# CPU.net
KiCad netlist of a schematic drawn in Altium Designer
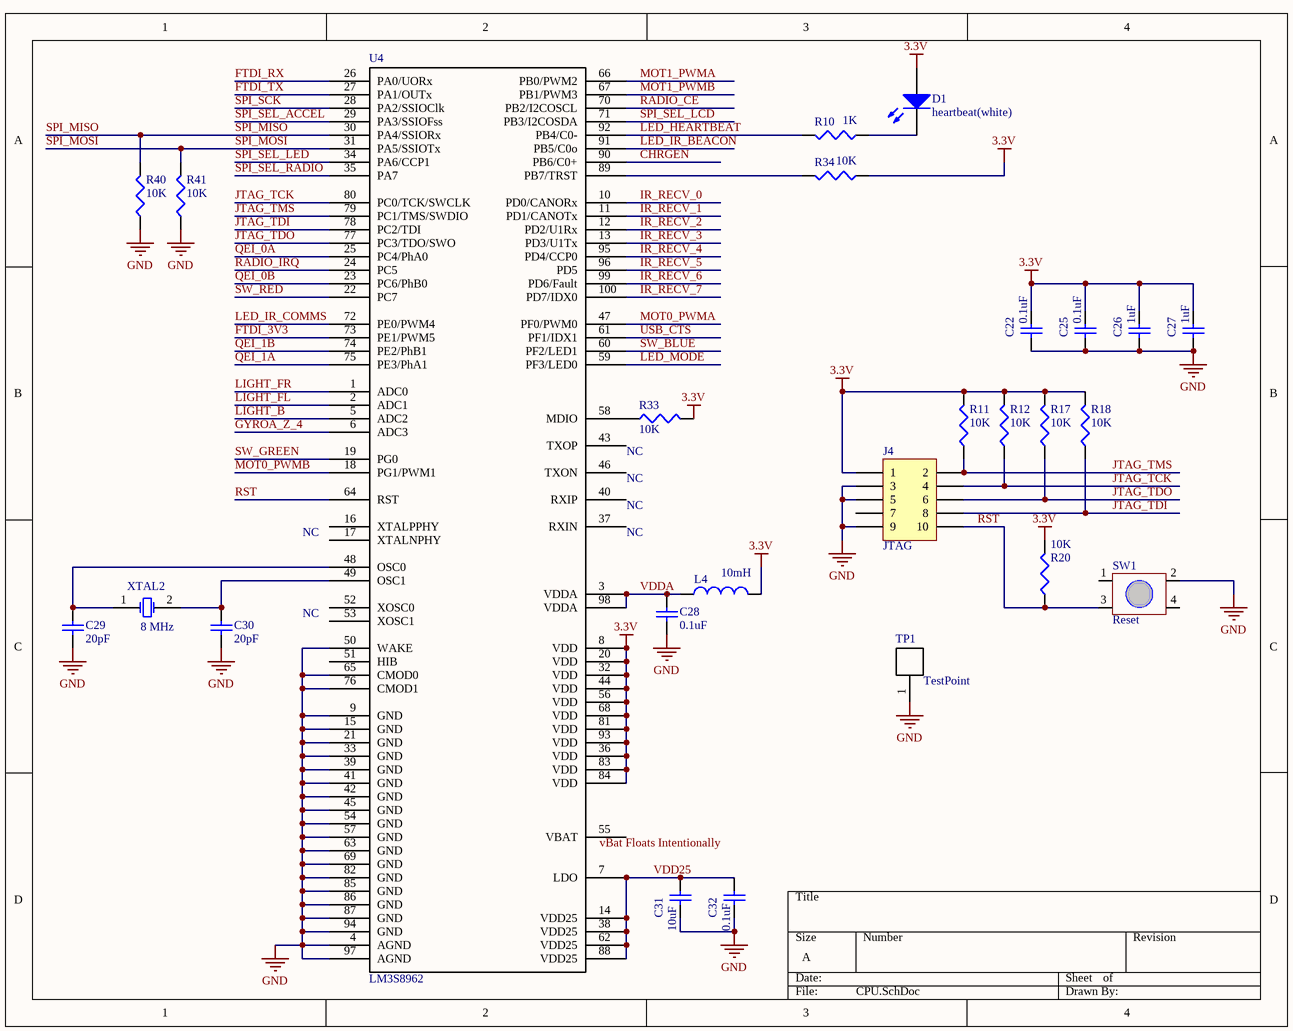
[diagram p0: CPU.SchDoc]

(export (version "E")
  (design (tool "Eeschema 10.0.6"))
  (components
    (comp (ref "C22")
      (value "0.1uF")
      (footprint "CAPC1005L")
      (description "Capacitor (Semiconductor SIM Model)")
      (fields (field (name "Comment") "Cap Semi") (field (name "PUBLISHER") "Altium Limited"))
      (libsource (lib "Miscellaneous Devices") (part "Cap Semi"))
    )
    (comp (ref "C25")
      (value "0.1uF")
      (footprint "CAPC1005L")
      (description "Capacitor (Semiconductor SIM Model)")
      (fields (field (name "Comment") "Cap Semi") (field (name "PUBLISHER") "Altium Limited"))
      (libsource (lib "Miscellaneous Devices") (part "Cap Semi"))
    )
    (comp (ref "C26")
      (value "1uF")
      (footprint "CAPC1608L")
      (description "Capacitor (Semiconductor SIM Model)")
      (fields (field (name "Comment") "Cap Semi") (field (name "PUBLISHER") "Altium Limited"))
      (libsource (lib "Miscellaneous Devices") (part "Cap Semi"))
    )
    (comp (ref "C27")
      (value "1uF")
      (footprint "CAPC1608L")
      (description "Capacitor (Semiconductor SIM Model)")
      (fields (field (name "Comment") "Cap Semi") (field (name "PUBLISHER") "Altium Limited"))
      (libsource (lib "Miscellaneous Devices") (part "Cap Semi"))
    )
    (comp (ref "C28")
      (value "0.1uF")
      (footprint "CAPC1005L")
      (description "Capacitor (Semiconductor SIM Model)")
      (fields (field (name "Comment") "Cap Semi") (field (name "PUBLISHER") "Altium Limited"))
      (libsource (lib "Miscellaneous Devices") (part "Cap Semi"))
    )
    (comp (ref "C29")
      (value "20pF")
      (footprint "CAPC1005L")
      (description "Capacitor (Semiconductor SIM Model)")
      (fields (field (name "Comment") "Cap Semi") (field (name "PUBLISHER") "Altium Limited"))
      (libsource (lib "Miscellaneous Devices") (part "Cap Semi"))
    )
    (comp (ref "C30")
      (value "20pF")
      (footprint "CAPC1005L")
      (description "Capacitor (Semiconductor SIM Model)")
      (fields (field (name "Comment") "Cap Semi") (field (name "PUBLISHER") "Altium Limited"))
      (libsource (lib "Miscellaneous Devices") (part "Cap Semi"))
    )
    (comp (ref "C31")
      (value "10uF")
      (footprint "CAPC1608L")
      (description "Capacitor (Semiconductor SIM Model)")
      (fields (field (name "Comment") "Cap Semi") (field (name "PUBLISHER") "Altium Limited"))
      (libsource (lib "Miscellaneous Devices") (part "Cap Semi"))
    )
    (comp (ref "C32")
      (value "0.1uF")
      (footprint "CAPC1005L")
      (description "Capacitor (Semiconductor SIM Model)")
      (fields (field (name "Comment") "Cap Semi") (field (name "PUBLISHER") "Altium Limited"))
      (libsource (lib "Miscellaneous Devices") (part "Cap Semi"))
    )
    (comp (ref "D1")
      (value "heartbeat(white)")
      (footprint "INDC2012L")
      (description "Typical RED, GREEN, YELLOW, AMBER GaAs LED")
      (fields (field (name "PUBLISHER") "Altium Limited"))
      (libsource (lib "Miscellaneous Devices") (part "LED2"))
    )
    (comp (ref "J4")
      (value "JTAG")
      (footprint "JTAG-10")
      (description "Header, 5-Pin, Dual row, Right Angle")
      (fields (field (name "PUBLISHER") "Altium Limited"))
      (libsource (lib "Miscellaneous Connectors") (part "Header 5X2H"))
    )
    (comp (ref "L4")
      (value "10mH")
      (footprint "INDC2012L")
      (description "Inductor")
      (fields (field (name "PUBLISHER") "Altium Limited"))
      (libsource (lib "Miscellaneous Devices") (part "Inductor"))
    )
    (comp (ref "R10")
      (value "1K")
      (footprint "RESC1608L")
      (description "Resistor")
      (fields (field (name "Comment") "Res3") (field (name "PUBLISHER") "Altium Limited"))
      (libsource (lib "Miscellaneous Devices") (part "Res3"))
    )
    (comp (ref "R11")
      (value "10K")
      (footprint "RESC1608L")
      (description "Resistor")
      (fields (field (name "Comment") "Res3") (field (name "PUBLISHER") "Altium Limited"))
      (libsource (lib "Miscellaneous Devices") (part "Res3"))
    )
    (comp (ref "R12")
      (value "10K")
      (footprint "RESC1608L")
      (description "Resistor")
      (fields (field (name "Comment") "Res3") (field (name "PUBLISHER") "Altium Limited"))
      (libsource (lib "Miscellaneous Devices") (part "Res3"))
    )
    (comp (ref "R17")
      (value "10K")
      (footprint "RESC1608L")
      (description "Resistor")
      (fields (field (name "Comment") "Res3") (field (name "PUBLISHER") "Altium Limited"))
      (libsource (lib "Miscellaneous Devices") (part "Res3"))
    )
    (comp (ref "R18")
      (value "10K")
      (footprint "RESC1608L")
      (description "Resistor")
      (fields (field (name "Comment") "Res3") (field (name "PUBLISHER") "Altium Limited"))
      (libsource (lib "Miscellaneous Devices") (part "Res3"))
    )
    (comp (ref "R20")
      (value "10K")
      (footprint "RESC1608L")
      (description "Resistor")
      (fields (field (name "Comment") "Res3") (field (name "PUBLISHER") "Altium Limited"))
      (libsource (lib "Miscellaneous Devices") (part "Res3"))
    )
    (comp (ref "R33")
      (value "10K")
      (footprint "RESC1608L")
      (description "Resistor")
      (fields (field (name "Comment") "Res3") (field (name "PUBLISHER") "Altium Limited"))
      (libsource (lib "Miscellaneous Devices") (part "Res3"))
    )
    (comp (ref "R34")
      (value "10K")
      (footprint "RESC1608L")
      (description "Resistor")
      (fields (field (name "Comment") "Res3") (field (name "PUBLISHER") "Altium Limited"))
      (libsource (lib "Miscellaneous Devices") (part "Res3"))
    )
    (comp (ref "R40")
      (value "10K")
      (footprint "RESC1608L")
      (description "Resistor")
      (fields (field (name "Comment") "Res3") (field (name "PUBLISHER") "Altium Limited"))
      (libsource (lib "Miscellaneous Devices") (part "Res3"))
    )
    (comp (ref "R41")
      (value "10K")
      (footprint "RESC1608L")
      (description "Resistor")
      (fields (field (name "Comment") "Res3") (field (name "PUBLISHER") "Altium Limited"))
      (libsource (lib "Miscellaneous Devices") (part "Res3"))
    )
    (comp (ref "SW1")
      (value "Reset")
      (footprint "SwitchTall-TL330")
      (libsource (lib "mrone") (part "Switch-TL330"))
    )
    (comp (ref "TP1")
      (value "TestPoint")
      (footprint "TestPoint")
      (libsource (lib "mrone") (part "TestPoint"))
    )
    (comp (ref "U4")
      (value "LM3S8962")
      (footprint "LQFP-100")
      (libsource (lib "Schematic Components") (part "LM3S8962"))
    )
    (comp (ref "XTAL2")
      (value "8 MHz")
      (footprint "RESC5025L")
      (description "Crystal Oscillator")
      (fields (field (name "PUBLISHER") "Altium Limited"))
      (libsource (lib "Miscellaneous Devices") (part "XTAL"))
    )
  )
  (nets
    (net (code "1") (name "/CHRGEN") (class "Default")
      (node (ref "U4") (pin "90") (pinfunction "PB6/C0+_90") (pintype "passive"))
    )
    (net (code "2") (name "/FTDI_3V3") (class "Default")
      (node (ref "U4") (pin "73") (pinfunction "PE1/PWM5_73") (pintype "passive"))
    )
    (net (code "3") (name "/FTDI_RX") (class "Default")
      (node (ref "U4") (pin "26") (pinfunction "PA0/UORx_26") (pintype "passive"))
    )
    (net (code "4") (name "/FTDI_TX") (class "Default")
      (node (ref "U4") (pin "27") (pinfunction "PA1/OUTx_27") (pintype "passive"))
    )
    (net (code "5") (name "/GYROA_Z_4") (class "Default")
      (node (ref "U4") (pin "6") (pinfunction "ADC3_6") (pintype "passive"))
    )
    (net (code "6") (name "/IR_RECV_0") (class "Default")
      (node (ref "U4") (pin "10") (pinfunction "PD0/CANORx_10") (pintype "passive"))
    )
    (net (code "7") (name "/IR_RECV_1") (class "Default")
      (node (ref "U4") (pin "11") (pinfunction "PD1/CANOTx_11") (pintype "passive"))
    )
    (net (code "8") (name "/IR_RECV_2") (class "Default")
      (node (ref "U4") (pin "12") (pinfunction "PD2/U1Rx_12") (pintype "passive"))
    )
    (net (code "9") (name "/IR_RECV_3") (class "Default")
      (node (ref "U4") (pin "13") (pinfunction "PD3/U1Tx_13") (pintype "passive"))
    )
    (net (code "10") (name "/IR_RECV_4") (class "Default")
      (node (ref "U4") (pin "95") (pinfunction "PD4/CCP0_95") (pintype "passive"))
    )
    (net (code "11") (name "/IR_RECV_5") (class "Default")
      (node (ref "U4") (pin "96") (pinfunction "PD5_96") (pintype "passive"))
    )
    (net (code "12") (name "/IR_RECV_6") (class "Default")
      (node (ref "U4") (pin "99") (pinfunction "PD6/Fault_99") (pintype "passive"))
    )
    (net (code "13") (name "/IR_RECV_7") (class "Default")
      (node (ref "U4") (pin "100") (pinfunction "PD7/IDX0_100") (pintype "passive"))
    )
    (net (code "14") (name "/JTAG_TCK") (class "Default")
      (node (ref "J4") (pin "4") (pinfunction "4_4") (pintype "passive"))
      (node (ref "R12") (pin "1") (pinfunction "1_1") (pintype "passive"))
      (node (ref "U4") (pin "80") (pinfunction "PC0/TCK/SWCLK_80") (pintype "passive"))
    )
    (net (code "15") (name "/JTAG_TDI") (class "Default")
      (node (ref "J4") (pin "8") (pinfunction "8_8") (pintype "passive"))
      (node (ref "R18") (pin "1") (pinfunction "1_1") (pintype "passive"))
      (node (ref "U4") (pin "78") (pinfunction "PC2/TDI_78") (pintype "passive"))
    )
    (net (code "16") (name "/JTAG_TDO") (class "Default")
      (node (ref "J4") (pin "6") (pinfunction "6_6") (pintype "passive"))
      (node (ref "R17") (pin "1") (pinfunction "1_1") (pintype "passive"))
      (node (ref "U4") (pin "77") (pinfunction "PC3/TDO/SWO_77") (pintype "passive"))
    )
    (net (code "17") (name "/JTAG_TMS") (class "Default")
      (node (ref "J4") (pin "2") (pinfunction "2_2") (pintype "passive"))
      (node (ref "R11") (pin "1") (pinfunction "1_1") (pintype "passive"))
      (node (ref "U4") (pin "79") (pinfunction "PC1/TMS/SWDIO_79") (pintype "passive"))
    )
    (net (code "18") (name "/LED_HEARTBEAT") (class "Default")
      (node (ref "R10") (pin "2") (pinfunction "2_2") (pintype "passive"))
      (node (ref "U4") (pin "92") (pinfunction "PB4/C0-_92") (pintype "passive"))
    )
    (net (code "19") (name "/LED_IR_BEACON") (class "Default")
      (node (ref "U4") (pin "91") (pinfunction "PB5/C0o_91") (pintype "passive"))
    )
    (net (code "20") (name "/LED_IR_COMMS") (class "Default")
      (node (ref "U4") (pin "72") (pinfunction "PE0/PWM4_72") (pintype "passive"))
    )
    (net (code "21") (name "/LED_MODE") (class "Default")
      (node (ref "U4") (pin "59") (pinfunction "PF3/LED0_59") (pintype "passive"))
    )
    (net (code "22") (name "/LIGHT_B") (class "Default")
      (node (ref "U4") (pin "5") (pinfunction "ADC2_5") (pintype "passive"))
    )
    (net (code "23") (name "/LIGHT_FL") (class "Default")
      (node (ref "U4") (pin "2") (pinfunction "ADC1_2") (pintype "passive"))
    )
    (net (code "24") (name "/LIGHT_FR") (class "Default")
      (node (ref "U4") (pin "1") (pinfunction "ADC0_1") (pintype "passive"))
    )
    (net (code "25") (name "/MOT0_PWMA") (class "Default")
      (node (ref "U4") (pin "47") (pinfunction "PF0/PWM0_47") (pintype "passive"))
    )
    (net (code "26") (name "/MOT0_PWMB") (class "Default")
      (node (ref "U4") (pin "18") (pinfunction "PG1/PWM1_18") (pintype "passive"))
    )
    (net (code "27") (name "/MOT1_PWMA") (class "Default")
      (node (ref "U4") (pin "66") (pinfunction "PB0/PWM2_66") (pintype "passive"))
    )
    (net (code "28") (name "/MOT1_PWMB") (class "Default")
      (node (ref "U4") (pin "67") (pinfunction "PB1/PWM3_67") (pintype "passive"))
    )
    (net (code "29") (name "/QEI_0A") (class "Default")
      (node (ref "U4") (pin "25") (pinfunction "PC4/PhA0_25") (pintype "passive"))
    )
    (net (code "30") (name "/QEI_0B") (class "Default")
      (node (ref "U4") (pin "23") (pinfunction "PC6/PhB0_23") (pintype "passive"))
    )
    (net (code "31") (name "/QEI_1A") (class "Default")
      (node (ref "U4") (pin "75") (pinfunction "PE3/PhA1_75") (pintype "passive"))
    )
    (net (code "32") (name "/QEI_1B") (class "Default")
      (node (ref "U4") (pin "74") (pinfunction "PE2/PhB1_74") (pintype "passive"))
    )
    (net (code "33") (name "/RADIO_CE") (class "Default")
      (node (ref "U4") (pin "70") (pinfunction "PB2/I2COSCL_70") (pintype "passive"))
    )
    (net (code "34") (name "/RADIO_IRQ") (class "Default")
      (node (ref "U4") (pin "24") (pinfunction "PC5_24") (pintype "passive"))
    )
    (net (code "35") (name "/RST") (class "Default")
      (node (ref "J4") (pin "10") (pinfunction "10_10") (pintype "passive"))
      (node (ref "R20") (pin "1") (pinfunction "1_1") (pintype "passive"))
      (node (ref "SW1") (pin "3") (pinfunction "3_3") (pintype "passive"))
      (node (ref "U4") (pin "64") (pinfunction "RST_64") (pintype "passive"))
    )
    (net (code "36") (name "/SPI_MISO") (class "Default")
      (node (ref "R40") (pin "2") (pinfunction "2_2") (pintype "passive"))
      (node (ref "U4") (pin "30") (pinfunction "PA4/SSIORx_30") (pintype "passive"))
    )
    (net (code "37") (name "/SPI_MOSI") (class "Default")
      (node (ref "R41") (pin "2") (pinfunction "2_2") (pintype "passive"))
      (node (ref "U4") (pin "31") (pinfunction "PA5/SSIOTx_31") (pintype "passive"))
    )
    (net (code "38") (name "/SPI_SCK") (class "Default")
      (node (ref "U4") (pin "28") (pinfunction "PA2/SSIOClk_28") (pintype "passive"))
    )
    (net (code "39") (name "/SPI_SEL_ACCEL") (class "Default")
      (node (ref "U4") (pin "29") (pinfunction "PA3/SSIOFss_29") (pintype "passive"))
    )
    (net (code "40") (name "/SPI_SEL_LCD") (class "Default")
      (node (ref "U4") (pin "71") (pinfunction "PB3/I2COSDA_71") (pintype "passive"))
    )
    (net (code "41") (name "/SPI_SEL_LED") (class "Default")
      (node (ref "U4") (pin "34") (pinfunction "PA6/CCP1_34") (pintype "passive"))
    )
    (net (code "42") (name "/SPI_SEL_RADIO") (class "Default")
      (node (ref "U4") (pin "35") (pinfunction "PA7_35") (pintype "passive"))
    )
    (net (code "43") (name "/SW_BLUE") (class "Default")
      (node (ref "U4") (pin "60") (pinfunction "PF2/LED1_60") (pintype "passive"))
    )
    (net (code "44") (name "/SW_GREEN") (class "Default")
      (node (ref "U4") (pin "19") (pinfunction "PG0_19") (pintype "passive"))
    )
    (net (code "45") (name "/SW_RED") (class "Default")
      (node (ref "U4") (pin "22") (pinfunction "PC7_22") (pintype "passive"))
    )
    (net (code "46") (name "/USB_CTS") (class "Default")
      (node (ref "U4") (pin "61") (pinfunction "PF1/IDX1_61") (pintype "passive"))
    )
    (net (code "47") (name "/VDD25") (class "Default")
      (node (ref "C31") (pin "2") (pinfunction "2_2") (pintype "passive"))
      (node (ref "C32") (pin "2") (pinfunction "2_2") (pintype "passive"))
      (node (ref "U4") (pin "14") (pinfunction "VDD25_14") (pintype "passive"))
      (node (ref "U4") (pin "38") (pinfunction "VDD25_38") (pintype "passive"))
      (node (ref "U4") (pin "62") (pinfunction "VDD25_62") (pintype "passive"))
      (node (ref "U4") (pin "7") (pinfunction "LDO_7") (pintype "passive"))
      (node (ref "U4") (pin "88") (pinfunction "VDD25_88") (pintype "passive"))
    )
    (net (code "48") (name "/VDDA") (class "Default")
      (node (ref "C28") (pin "2") (pinfunction "2_2") (pintype "passive"))
      (node (ref "L4") (pin "1") (pinfunction "1_1") (pintype "passive"))
      (node (ref "U4") (pin "3") (pinfunction "VDDA_3") (pintype "passive"))
      (node (ref "U4") (pin "98") (pinfunction "VDDA_98") (pintype "passive"))
    )
    (net (code "49") (name "3.3V") (class "Default")
      (node (ref "C22") (pin "2") (pinfunction "2_2") (pintype "passive"))
      (node (ref "C25") (pin "2") (pinfunction "2_2") (pintype "passive"))
      (node (ref "C26") (pin "2") (pinfunction "2_2") (pintype "passive"))
      (node (ref "C27") (pin "2") (pinfunction "2_2") (pintype "passive"))
      (node (ref "D1") (pin "1") (pinfunction "A_1") (pintype "passive"))
      (node (ref "J4") (pin "1") (pinfunction "1_1") (pintype "passive"))
      (node (ref "L4") (pin "2") (pinfunction "2_2") (pintype "passive"))
      (node (ref "R11") (pin "2") (pinfunction "2_2") (pintype "passive"))
      (node (ref "R12") (pin "2") (pinfunction "2_2") (pintype "passive"))
      (node (ref "R17") (pin "2") (pinfunction "2_2") (pintype "passive"))
      (node (ref "R18") (pin "2") (pinfunction "2_2") (pintype "passive"))
      (node (ref "R20") (pin "2") (pinfunction "2_2") (pintype "passive"))
      (node (ref "R33") (pin "2") (pinfunction "2_2") (pintype "passive"))
      (node (ref "R34") (pin "1") (pinfunction "1_1") (pintype "passive"))
      (node (ref "U4") (pin "20") (pinfunction "VDD_20") (pintype "passive"))
      (node (ref "U4") (pin "32") (pinfunction "VDD_32") (pintype "passive"))
      (node (ref "U4") (pin "36") (pinfunction "VDD_36") (pintype "passive"))
      (node (ref "U4") (pin "44") (pinfunction "VDD_44") (pintype "passive"))
      (node (ref "U4") (pin "56") (pinfunction "VDD_56") (pintype "passive"))
      (node (ref "U4") (pin "68") (pinfunction "VDD_68") (pintype "passive"))
      (node (ref "U4") (pin "8") (pinfunction "VDD_8") (pintype "passive"))
      (node (ref "U4") (pin "81") (pinfunction "VDD_81") (pintype "passive"))
      (node (ref "U4") (pin "83") (pinfunction "VDD_83") (pintype "passive"))
      (node (ref "U4") (pin "84") (pinfunction "VDD_84") (pintype "passive"))
      (node (ref "U4") (pin "93") (pinfunction "VDD_93") (pintype "passive"))
    )
    (net (code "50") (name "GND") (class "Default")
      (node (ref "C22") (pin "1") (pinfunction "1_1") (pintype "passive"))
      (node (ref "C25") (pin "1") (pinfunction "1_1") (pintype "passive"))
      (node (ref "C26") (pin "1") (pinfunction "1_1") (pintype "passive"))
      (node (ref "C27") (pin "1") (pinfunction "1_1") (pintype "passive"))
      (node (ref "C28") (pin "1") (pinfunction "1_1") (pintype "passive"))
      (node (ref "C29") (pin "1") (pinfunction "1_1") (pintype "passive"))
      (node (ref "C30") (pin "1") (pinfunction "1_1") (pintype "passive"))
      (node (ref "C31") (pin "1") (pinfunction "1_1") (pintype "passive"))
      (node (ref "C32") (pin "1") (pinfunction "1_1") (pintype "passive"))
      (node (ref "J4") (pin "3") (pinfunction "3_3") (pintype "passive"))
      (node (ref "J4") (pin "5") (pinfunction "5_5") (pintype "passive"))
      (node (ref "J4") (pin "9") (pinfunction "9_9") (pintype "passive"))
      (node (ref "R40") (pin "1") (pinfunction "1_1") (pintype "passive"))
      (node (ref "R41") (pin "1") (pinfunction "1_1") (pintype "passive"))
      (node (ref "SW1") (pin "2") (pinfunction "2_2") (pintype "passive"))
      (node (ref "TP1") (pin "1") (pintype "passive"))
      (node (ref "U4") (pin "15") (pinfunction "GND_15") (pintype "passive"))
      (node (ref "U4") (pin "21") (pinfunction "GND_21") (pintype "passive"))
      (node (ref "U4") (pin "33") (pinfunction "GND_33") (pintype "passive"))
      (node (ref "U4") (pin "39") (pinfunction "GND_39") (pintype "passive"))
      (node (ref "U4") (pin "4") (pinfunction "AGND_4") (pintype "passive"))
      (node (ref "U4") (pin "41") (pinfunction "GND_41") (pintype "passive"))
      (node (ref "U4") (pin "42") (pinfunction "GND_42") (pintype "passive"))
      (node (ref "U4") (pin "45") (pinfunction "GND_45") (pintype "passive"))
      (node (ref "U4") (pin "50") (pinfunction "WAKE_50") (pintype "passive"))
      (node (ref "U4") (pin "54") (pinfunction "GND_54") (pintype "passive"))
      (node (ref "U4") (pin "57") (pinfunction "GND_57") (pintype "passive"))
      (node (ref "U4") (pin "63") (pinfunction "GND_63") (pintype "passive"))
      (node (ref "U4") (pin "65") (pinfunction "CMOD0_65") (pintype "passive"))
      (node (ref "U4") (pin "69") (pinfunction "GND_69") (pintype "passive"))
      (node (ref "U4") (pin "76") (pinfunction "CMOD1_76") (pintype "passive"))
      (node (ref "U4") (pin "82") (pinfunction "GND_82") (pintype "passive"))
      (node (ref "U4") (pin "85") (pinfunction "GND_85") (pintype "passive"))
      (node (ref "U4") (pin "86") (pinfunction "GND_86") (pintype "passive"))
      (node (ref "U4") (pin "87") (pinfunction "GND_87") (pintype "passive"))
      (node (ref "U4") (pin "9") (pinfunction "GND_9") (pintype "passive"))
      (node (ref "U4") (pin "94") (pinfunction "GND_94") (pintype "passive"))
      (node (ref "U4") (pin "97") (pinfunction "AGND_97") (pintype "passive"))
    )
    (net (code "51") (name "Net-(D1-K)") (class "Default")
      (node (ref "D1") (pin "2") (pinfunction "K_2") (pintype "passive"))
      (node (ref "R10") (pin "1") (pinfunction "1_1") (pintype "passive"))
    )
    (net (code "52") (name "Net-(U4-MDIO)") (class "Default")
      (node (ref "R33") (pin "1") (pinfunction "1_1") (pintype "passive"))
      (node (ref "U4") (pin "58") (pinfunction "MDIO_58") (pintype "passive"))
    )
    (net (code "53") (name "Net-(U4-OSC0)") (class "Default")
      (node (ref "C29") (pin "2") (pinfunction "2_2") (pintype "passive"))
      (node (ref "U4") (pin "48") (pinfunction "OSC0_48") (pintype "passive"))
      (node (ref "XTAL2") (pin "1") (pinfunction "OSC1_1") (pintype "passive"))
    )
    (net (code "54") (name "Net-(U4-OSC1)") (class "Default")
      (node (ref "C30") (pin "2") (pinfunction "2_2") (pintype "passive"))
      (node (ref "U4") (pin "49") (pinfunction "OSC1_49") (pintype "passive"))
      (node (ref "XTAL2") (pin "2") (pinfunction "OSC2_2") (pintype "passive"))
    )
    (net (code "55") (name "Net-(U4-PB7{slash}TRST)") (class "Default")
      (node (ref "R34") (pin "2") (pinfunction "2_2") (pintype "passive"))
      (node (ref "U4") (pin "89") (pinfunction "PB7/TRST_89") (pintype "passive"))
    )
    (net (code "56") (name "unconnected-(J4-Pad7)") (class "Default")
      (node (ref "J4") (pin "7") (pinfunction "7_7") (pintype "passive"))
    )
    (net (code "57") (name "unconnected-(SW1-Pad1)") (class "Default")
      (node (ref "SW1") (pin "1") (pinfunction "1_1") (pintype "passive"))
    )
    (net (code "58") (name "unconnected-(SW1-Pad4)") (class "Default")
      (node (ref "SW1") (pin "4") (pinfunction "4_4") (pintype "passive"))
    )
    (net (code "59") (name "unconnected-(U4-HIB-Pad51)") (class "Default")
      (node (ref "U4") (pin "51") (pinfunction "HIB_51") (pintype "passive"))
    )
    (net (code "60") (name "unconnected-(U4-RXIN-Pad37)") (class "Default")
      (node (ref "U4") (pin "37") (pinfunction "RXIN_37") (pintype "passive"))
    )
    (net (code "61") (name "unconnected-(U4-RXIP-Pad40)") (class "Default")
      (node (ref "U4") (pin "40") (pinfunction "RXIP_40") (pintype "passive"))
    )
    (net (code "62") (name "unconnected-(U4-TXON-Pad46)") (class "Default")
      (node (ref "U4") (pin "46") (pinfunction "TXON_46") (pintype "passive"))
    )
    (net (code "63") (name "unconnected-(U4-TXOP-Pad43)") (class "Default")
      (node (ref "U4") (pin "43") (pinfunction "TXOP_43") (pintype "passive"))
    )
    (net (code "64") (name "unconnected-(U4-VBAT-Pad55)") (class "Default")
      (node (ref "U4") (pin "55") (pinfunction "VBAT_55") (pintype "passive"))
    )
    (net (code "65") (name "unconnected-(U4-XOSC0-Pad52)") (class "Default")
      (node (ref "U4") (pin "52") (pinfunction "XOSC0_52") (pintype "passive"))
    )
    (net (code "66") (name "unconnected-(U4-XOSC1-Pad53)") (class "Default")
      (node (ref "U4") (pin "53") (pinfunction "XOSC1_53") (pintype "passive"))
    )
    (net (code "67") (name "unconnected-(U4-XTALNPHY-Pad17)") (class "Default")
      (node (ref "U4") (pin "17") (pinfunction "XTALNPHY_17") (pintype "passive"))
    )
    (net (code "68") (name "unconnected-(U4-XTALPPHY-Pad16)") (class "Default")
      (node (ref "U4") (pin "16") (pinfunction "XTALPPHY_16") (pintype "passive"))
    )
  )
)
